# kitchenClock_v4.net
KiCad netlist of a schematic drawn in EAGLE
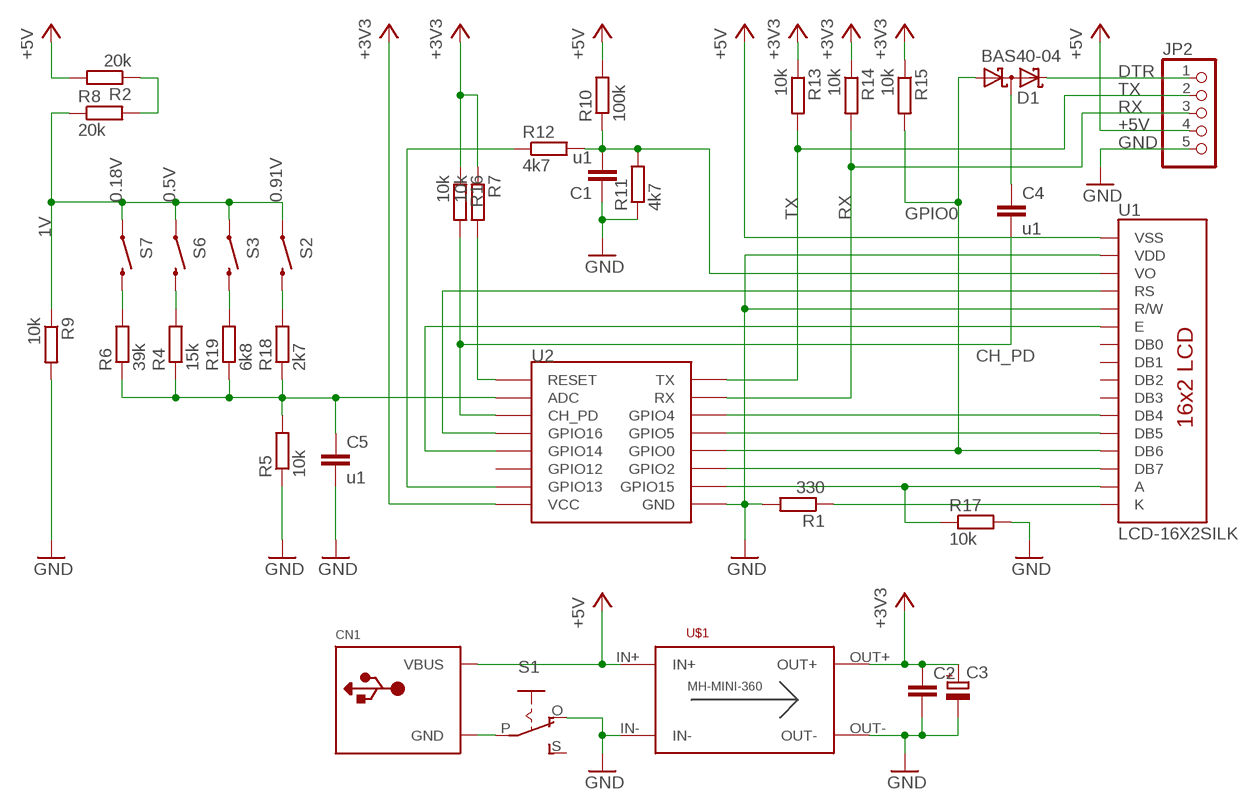
[diagram p0: schematic, sheet 1]

(export (version "E")
  (design (tool "Eeschema 10.0.6"))
  (components
    (comp (ref "C1")
      (value "u1")
      (footprint "eagle-import:C075-032X103")
      (libsource (lib "eagle-import") (part "C-EU075-032X103"))
    )
    (comp (ref "C2")
      (value "C-EU025-025X050")
      (footprint "eagle-import:C025-025X050")
      (libsource (lib "eagle-import") (part "C-EU025-025X050"))
    )
    (comp (ref "C3")
      (value "CPOL-EUTT2D5L")
      (footprint "eagle-import:TT2D5L")
      (libsource (lib "eagle-import") (part "CPOL-EUTT2D5L"))
    )
    (comp (ref "C4")
      (value "u1")
      (footprint "eagle-import:C075-032X103")
      (libsource (lib "eagle-import") (part "C-EU075-032X103"))
    )
    (comp (ref "C5")
      (value "u1")
      (footprint "eagle-import:C025-025X050")
      (libsource (lib "eagle-import") (part "C-EU025-025X050"))
    )
    (comp (ref "CN1")
      (value "USBPWR-ONLY")
      (footprint "eagle-import:USB-MINIB-THM")
      (libsource (lib "eagle-import") (part "USBPWR-ONLY"))
    )
    (comp (ref "D1")
      (value "BAS40-04")
      (footprint "eagle-import:SOT23")
      (libsource (lib "eagle-import") (part "BAS40-04"))
    )
    (comp (ref "JP2")
      (value "PINHD-1X5/90")
      (footprint "eagle-import:1X05_90")
      (libsource (lib "eagle-import") (part "PINHD-1X5/90"))
    )
    (comp (ref "R1")
      (value "330")
      (footprint "eagle-import:M0805")
      (libsource (lib "eagle-import") (part "R-EU_M0805"))
    )
    (comp (ref "R2")
      (value "20k")
      (footprint "eagle-import:0204_7")
      (libsource (lib "eagle-import") (part "R-EU_0204/7"))
    )
    (comp (ref "R4")
      (value "15k")
      (footprint "eagle-import:0204_7")
      (libsource (lib "eagle-import") (part "R-EU_0204/7"))
    )
    (comp (ref "R5")
      (value "10k")
      (footprint "eagle-import:0204_7")
      (libsource (lib "eagle-import") (part "R-EU_0204/7"))
    )
    (comp (ref "R6")
      (value "39k")
      (footprint "eagle-import:0204_7")
      (libsource (lib "eagle-import") (part "R-EU_0204/7"))
    )
    (comp (ref "R7")
      (value "10k")
      (footprint "eagle-import:0204_7")
      (libsource (lib "eagle-import") (part "R-EU_0204/7"))
    )
    (comp (ref "R8")
      (value "20k")
      (footprint "eagle-import:0204_7")
      (libsource (lib "eagle-import") (part "R-EU_0204/7"))
    )
    (comp (ref "R9")
      (value "10k")
      (footprint "eagle-import:0204_7")
      (libsource (lib "eagle-import") (part "R-EU_0204/7"))
    )
    (comp (ref "R10")
      (value "100k")
      (footprint "eagle-import:M0805")
      (libsource (lib "eagle-import") (part "R-EU_M0805"))
    )
    (comp (ref "R11")
      (value "4k7")
      (footprint "eagle-import:0204_7")
      (libsource (lib "eagle-import") (part "R-EU_0204/7"))
    )
    (comp (ref "R12")
      (value "4k7")
      (footprint "eagle-import:0207_10")
      (libsource (lib "eagle-import") (part "R-EU_0207/10"))
    )
    (comp (ref "R13")
      (value "10k")
      (footprint "eagle-import:0207_10")
      (libsource (lib "eagle-import") (part "R-EU_0207/10"))
    )
    (comp (ref "R14")
      (value "10k")
      (footprint "eagle-import:0207_10")
      (libsource (lib "eagle-import") (part "R-EU_0207/10"))
    )
    (comp (ref "R15")
      (value "10k")
      (footprint "eagle-import:0207_10")
      (libsource (lib "eagle-import") (part "R-EU_0207/10"))
    )
    (comp (ref "R16")
      (value "10k")
      (footprint "eagle-import:M0805")
      (libsource (lib "eagle-import") (part "R-EU_M0805"))
    )
    (comp (ref "R17")
      (value "10k")
      (footprint "eagle-import:M0805")
      (libsource (lib "eagle-import") (part "R-EU_M0805"))
    )
    (comp (ref "R18")
      (value "2k7")
      (footprint "eagle-import:0204_7")
      (libsource (lib "eagle-import") (part "R-EU_0204/7"))
    )
    (comp (ref "R19")
      (value "6k8")
      (footprint "eagle-import:0204_7")
      (libsource (lib "eagle-import") (part "R-EU_0204/7"))
    )
    (comp (ref "S1")
      (value "EG1218S")
      (footprint "eagle-import:EG1218")
      (libsource (lib "eagle-import") (part "EG1218S"))
    )
    (comp (ref "S2")
      (value "SWITCH-MOMENTARY-2PTH")
      (footprint "eagle-import:TACTILE-PTH")
      (libsource (lib "eagle-import") (part "SWITCH-MOMENTARY-2PTH"))
    )
    (comp (ref "S3")
      (value "SWITCH-MOMENTARY-2PTH")
      (footprint "eagle-import:TACTILE-PTH")
      (libsource (lib "eagle-import") (part "SWITCH-MOMENTARY-2PTH"))
    )
    (comp (ref "S6")
      (value "SWITCH-MOMENTARY-2PTH")
      (footprint "eagle-import:TACTILE-PTH")
      (libsource (lib "eagle-import") (part "SWITCH-MOMENTARY-2PTH"))
    )
    (comp (ref "S7")
      (value "SWITCH-MOMENTARY-2PTH")
      (footprint "eagle-import:TACTILE-PTH")
      (libsource (lib "eagle-import") (part "SWITCH-MOMENTARY-2PTH"))
    )
    (comp (ref "U$1")
      (value "DC-DC_CONV_MINISTD")
      (footprint "eagle-import:DC-DC_CONV_MINI")
      (libsource (lib "eagle-import") (part "DC-DC_CONV_MINISTD"))
    )
    (comp (ref "U1")
      (value "LCD-16X2SILK")
      (footprint "eagle-import:LCD-16X2")
      (libsource (lib "eagle-import") (part "LCD-16X2SILK"))
    )
    (comp (ref "U2")
      (value "ESP12EDIP")
      (footprint "eagle-import:ESP-12-BREAKOUT")
      (libsource (lib "eagle-import") (part "ESP12EDIP"))
    )
  )
  (nets
    (net (code "1") (name "+3V3") (class "Default")
      (node (ref "C2") (pin "1") (pinfunction "1_1") (pintype "passive"))
      (node (ref "C3") (pin "+") (pinfunction "+_+") (pintype "passive"))
      (node (ref "R13") (pin "1") (pinfunction "1_1") (pintype "passive"))
      (node (ref "R14") (pin "1") (pinfunction "1_1") (pintype "passive"))
      (node (ref "R15") (pin "1") (pinfunction "1_1") (pintype "passive"))
      (node (ref "R16") (pin "1") (pinfunction "1_1") (pintype "passive"))
      (node (ref "R7") (pin "1") (pinfunction "1_1") (pintype "passive"))
      (node (ref "U$1") (pin "OUT+") (pinfunction "OUT+_OUT+") (pintype "bidirectional"))
      (node (ref "U2") (pin "P$1") (pinfunction "VCC_P$1") (pintype "bidirectional"))
    )
    (net (code "2") (name "+5V") (class "Default")
      (node (ref "CN1") (pin "VBUS") (pinfunction "VBUS_VBUS") (pintype "power_in"))
      (node (ref "JP2") (pin "4") (pinfunction "4_4") (pintype "passive"))
      (node (ref "R10") (pin "2") (pinfunction "2_2") (pintype "passive"))
      (node (ref "R2") (pin "2") (pinfunction "2_2") (pintype "passive"))
      (node (ref "U$1") (pin "IN+") (pinfunction "IN+_IN+") (pintype "bidirectional"))
      (node (ref "U1") (pin "1") (pinfunction "VSS_1") (pintype "power_in"))
    )
    (net (code "3") (name "/1V") (class "Default")
      (node (ref "R8") (pin "1") (pinfunction "1_1") (pintype "passive"))
      (node (ref "R9") (pin "1") (pinfunction "1_1") (pintype "passive"))
      (node (ref "S2") (pin "1") (pinfunction "1_1") (pintype "passive"))
      (node (ref "S3") (pin "1") (pinfunction "1_1") (pintype "passive"))
      (node (ref "S6") (pin "1") (pinfunction "1_1") (pintype "passive"))
      (node (ref "S7") (pin "1") (pinfunction "1_1") (pintype "passive"))
    )
    (net (code "4") (name "/CH_PD") (class "Default")
      (node (ref "C4") (pin "2") (pinfunction "2_2") (pintype "passive"))
      (node (ref "R16") (pin "2") (pinfunction "2_2") (pintype "passive"))
      (node (ref "U2") (pin "P$6") (pinfunction "CH_PD_P$6") (pintype "bidirectional"))
    )
    (net (code "5") (name "/DTR") (class "Default")
      (node (ref "D1") (pin "2") (pinfunction "C2_2") (pintype "passive"))
      (node (ref "JP2") (pin "1") (pinfunction "1_1") (pintype "passive"))
    )
    (net (code "6") (name "/GPIO0") (class "Default")
      (node (ref "D1") (pin "1") (pinfunction "A1_1") (pintype "passive"))
      (node (ref "R15") (pin "2") (pinfunction "2_2") (pintype "passive"))
      (node (ref "U1") (pin "13") (pinfunction "DB6_13") (pintype "bidirectional"))
      (node (ref "U2") (pin "P$12") (pinfunction "GPIO0_P$12") (pintype "bidirectional"))
    )
    (net (code "7") (name "/RX") (class "Default")
      (node (ref "JP2") (pin "3") (pinfunction "3_3") (pintype "passive"))
      (node (ref "R14") (pin "2") (pinfunction "2_2") (pintype "passive"))
      (node (ref "U2") (pin "P$15") (pinfunction "RX_P$15") (pintype "bidirectional"))
    )
    (net (code "8") (name "/TX") (class "Default")
      (node (ref "JP2") (pin "2") (pinfunction "2_2") (pintype "passive"))
      (node (ref "R13") (pin "2") (pinfunction "2_2") (pintype "passive"))
      (node (ref "U2") (pin "P$16") (pinfunction "TX_P$16") (pintype "bidirectional"))
    )
    (net (code "9") (name "GND") (class "Default")
      (node (ref "C1") (pin "1") (pinfunction "1_1") (pintype "passive"))
      (node (ref "C2") (pin "2") (pinfunction "2_2") (pintype "passive"))
      (node (ref "C3") (pin "-") (pinfunction "-_-") (pintype "passive"))
      (node (ref "C5") (pin "2") (pinfunction "2_2") (pintype "passive"))
      (node (ref "JP2") (pin "5") (pinfunction "5_5") (pintype "passive"))
      (node (ref "R1") (pin "2") (pinfunction "2_2") (pintype "passive"))
      (node (ref "R11") (pin "1") (pinfunction "1_1") (pintype "passive"))
      (node (ref "R17") (pin "2") (pinfunction "2_2") (pintype "passive"))
      (node (ref "R5") (pin "1") (pinfunction "1_1") (pintype "passive"))
      (node (ref "R9") (pin "2") (pinfunction "2_2") (pintype "passive"))
      (node (ref "S1") (pin "O") (pinfunction "O_O") (pintype "passive"))
      (node (ref "U$1") (pin "IN-") (pinfunction "IN-_IN-") (pintype "bidirectional"))
      (node (ref "U$1") (pin "OUT-") (pinfunction "OUT-_OUT-") (pintype "bidirectional"))
      (node (ref "U1") (pin "2") (pinfunction "VDD_2") (pintype "power_in"))
      (node (ref "U1") (pin "5") (pinfunction "R/W_5") (pintype "input"))
      (node (ref "U2") (pin "P$9") (pinfunction "GND_P$9") (pintype "bidirectional"))
    )
    (net (code "10") (name "Net-(CN1-GND-PadGND1)") (class "Default")
      (node (ref "CN1") (pin "GND") (pinfunction "GND_GND") (pintype "power_in"))
      (node (ref "CN1") (pin "GND1") (pinfunction "GND_GND1") (pintype "power_in"))
      (node (ref "CN1") (pin "GND2") (pinfunction "GND_GND2") (pintype "power_in"))
      (node (ref "CN1") (pin "GND3") (pinfunction "GND_GND3") (pintype "power_in"))
      (node (ref "CN1") (pin "GND4") (pinfunction "GND_GND4") (pintype "power_in"))
      (node (ref "S1") (pin "P") (pinfunction "P_P") (pintype "passive"))
    )
    (net (code "11") (name "Net-(D1-C1A2)") (class "Default")
      (node (ref "C4") (pin "1") (pinfunction "1_1") (pintype "passive"))
      (node (ref "D1") (pin "3") (pinfunction "C1A2_3") (pintype "passive"))
    )
    (net (code "12") (name "Net-(R2-Pad1)") (class "Default")
      (node (ref "R2") (pin "1") (pinfunction "1_1") (pintype "passive"))
      (node (ref "R8") (pin "2") (pinfunction "2_2") (pintype "passive"))
    )
    (net (code "13") (name "Net-(S2-2)") (class "Default")
      (node (ref "R18") (pin "2") (pinfunction "2_2") (pintype "passive"))
      (node (ref "S2") (pin "3") (pinfunction "2_3") (pintype "passive"))
    )
    (net (code "14") (name "Net-(S3-2)") (class "Default")
      (node (ref "R19") (pin "2") (pinfunction "2_2") (pintype "passive"))
      (node (ref "S3") (pin "3") (pinfunction "2_3") (pintype "passive"))
    )
    (net (code "15") (name "Net-(S6-2)") (class "Default")
      (node (ref "R4") (pin "2") (pinfunction "2_2") (pintype "passive"))
      (node (ref "S6") (pin "3") (pinfunction "2_3") (pintype "passive"))
    )
    (net (code "16") (name "Net-(S7-2)") (class "Default")
      (node (ref "R6") (pin "2") (pinfunction "2_2") (pintype "passive"))
      (node (ref "S7") (pin "3") (pinfunction "2_3") (pintype "passive"))
    )
    (net (code "17") (name "Net-(U1-A)") (class "Default")
      (node (ref "R17") (pin "1") (pinfunction "1_1") (pintype "passive"))
      (node (ref "U1") (pin "15") (pinfunction "A_15") (pintype "power_in"))
      (node (ref "U2") (pin "P$10") (pinfunction "GPIO15_P$10") (pintype "bidirectional"))
    )
    (net (code "18") (name "Net-(U1-DB4)") (class "Default")
      (node (ref "U1") (pin "11") (pinfunction "DB4_11") (pintype "bidirectional"))
      (node (ref "U2") (pin "P$14") (pinfunction "GPIO4_P$14") (pintype "bidirectional"))
    )
    (net (code "19") (name "Net-(U1-DB5)") (class "Default")
      (node (ref "U1") (pin "12") (pinfunction "DB5_12") (pintype "bidirectional"))
      (node (ref "U2") (pin "P$13") (pinfunction "GPIO5_P$13") (pintype "bidirectional"))
    )
    (net (code "20") (name "Net-(U1-DB7)") (class "Default")
      (node (ref "U1") (pin "14") (pinfunction "DB7_14") (pintype "bidirectional"))
      (node (ref "U2") (pin "P$11") (pinfunction "GPIO2_P$11") (pintype "bidirectional"))
    )
    (net (code "21") (name "Net-(U1-E)") (class "Default")
      (node (ref "U1") (pin "6") (pinfunction "E_6") (pintype "input"))
      (node (ref "U2") (pin "P$4") (pinfunction "GPIO14_P$4") (pintype "bidirectional"))
    )
    (net (code "22") (name "Net-(U1-K)") (class "Default")
      (node (ref "R1") (pin "1") (pinfunction "1_1") (pintype "passive"))
      (node (ref "U1") (pin "16") (pinfunction "K_16") (pintype "power_in"))
    )
    (net (code "23") (name "Net-(U1-RS)") (class "Default")
      (node (ref "U1") (pin "4") (pinfunction "RS_4") (pintype "input"))
      (node (ref "U2") (pin "P$5") (pinfunction "GPIO16_P$5") (pintype "bidirectional"))
    )
    (net (code "24") (name "Net-(U1-VO)") (class "Default")
      (node (ref "C1") (pin "2") (pinfunction "2_2") (pintype "passive"))
      (node (ref "R10") (pin "1") (pinfunction "1_1") (pintype "passive"))
      (node (ref "R11") (pin "2") (pinfunction "2_2") (pintype "passive"))
      (node (ref "R12") (pin "2") (pinfunction "2_2") (pintype "passive"))
      (node (ref "U1") (pin "3") (pinfunction "VO_3") (pintype "bidirectional"))
    )
    (net (code "25") (name "Net-(U2-ADC)") (class "Default")
      (node (ref "C5") (pin "1") (pinfunction "1_1") (pintype "passive"))
      (node (ref "R18") (pin "1") (pinfunction "1_1") (pintype "passive"))
      (node (ref "R19") (pin "1") (pinfunction "1_1") (pintype "passive"))
      (node (ref "R4") (pin "1") (pinfunction "1_1") (pintype "passive"))
      (node (ref "R5") (pin "2") (pinfunction "2_2") (pintype "passive"))
      (node (ref "R6") (pin "1") (pinfunction "1_1") (pintype "passive"))
      (node (ref "U2") (pin "P$7") (pinfunction "ADC_P$7") (pintype "bidirectional"))
    )
    (net (code "26") (name "Net-(U2-GPIO13)") (class "Default")
      (node (ref "R12") (pin "1") (pinfunction "1_1") (pintype "passive"))
      (node (ref "U2") (pin "P$2") (pinfunction "GPIO13_P$2") (pintype "bidirectional"))
    )
    (net (code "27") (name "Net-(U2-RESET)") (class "Default")
      (node (ref "R7") (pin "2") (pinfunction "2_2") (pintype "passive"))
      (node (ref "U2") (pin "P$8") (pinfunction "RESET_P$8") (pintype "bidirectional"))
    )
    (net (code "28") (name "unconnected-(S1-PadS)") (class "Default")
      (node (ref "S1") (pin "S") (pinfunction "S_S") (pintype "passive"))
    )
    (net (code "29") (name "unconnected-(U1-DB0-Pad7)") (class "Default")
      (node (ref "U1") (pin "7") (pinfunction "DB0_7") (pintype "bidirectional"))
    )
    (net (code "30") (name "unconnected-(U1-DB1-Pad8)") (class "Default")
      (node (ref "U1") (pin "8") (pinfunction "DB1_8") (pintype "bidirectional"))
    )
    (net (code "31") (name "unconnected-(U1-DB2-Pad9)") (class "Default")
      (node (ref "U1") (pin "9") (pinfunction "DB2_9") (pintype "bidirectional"))
    )
    (net (code "32") (name "unconnected-(U1-DB3-Pad10)") (class "Default")
      (node (ref "U1") (pin "10") (pinfunction "DB3_10") (pintype "bidirectional"))
    )
    (net (code "33") (name "unconnected-(U2-GPIO12-PadP$3)") (class "Default")
      (node (ref "U2") (pin "P$3") (pinfunction "GPIO12_P$3") (pintype "bidirectional"))
    )
  )
)
